# Lamp_Logic_Board_11.net
KiCad netlist of a schematic drawn in EAGLE
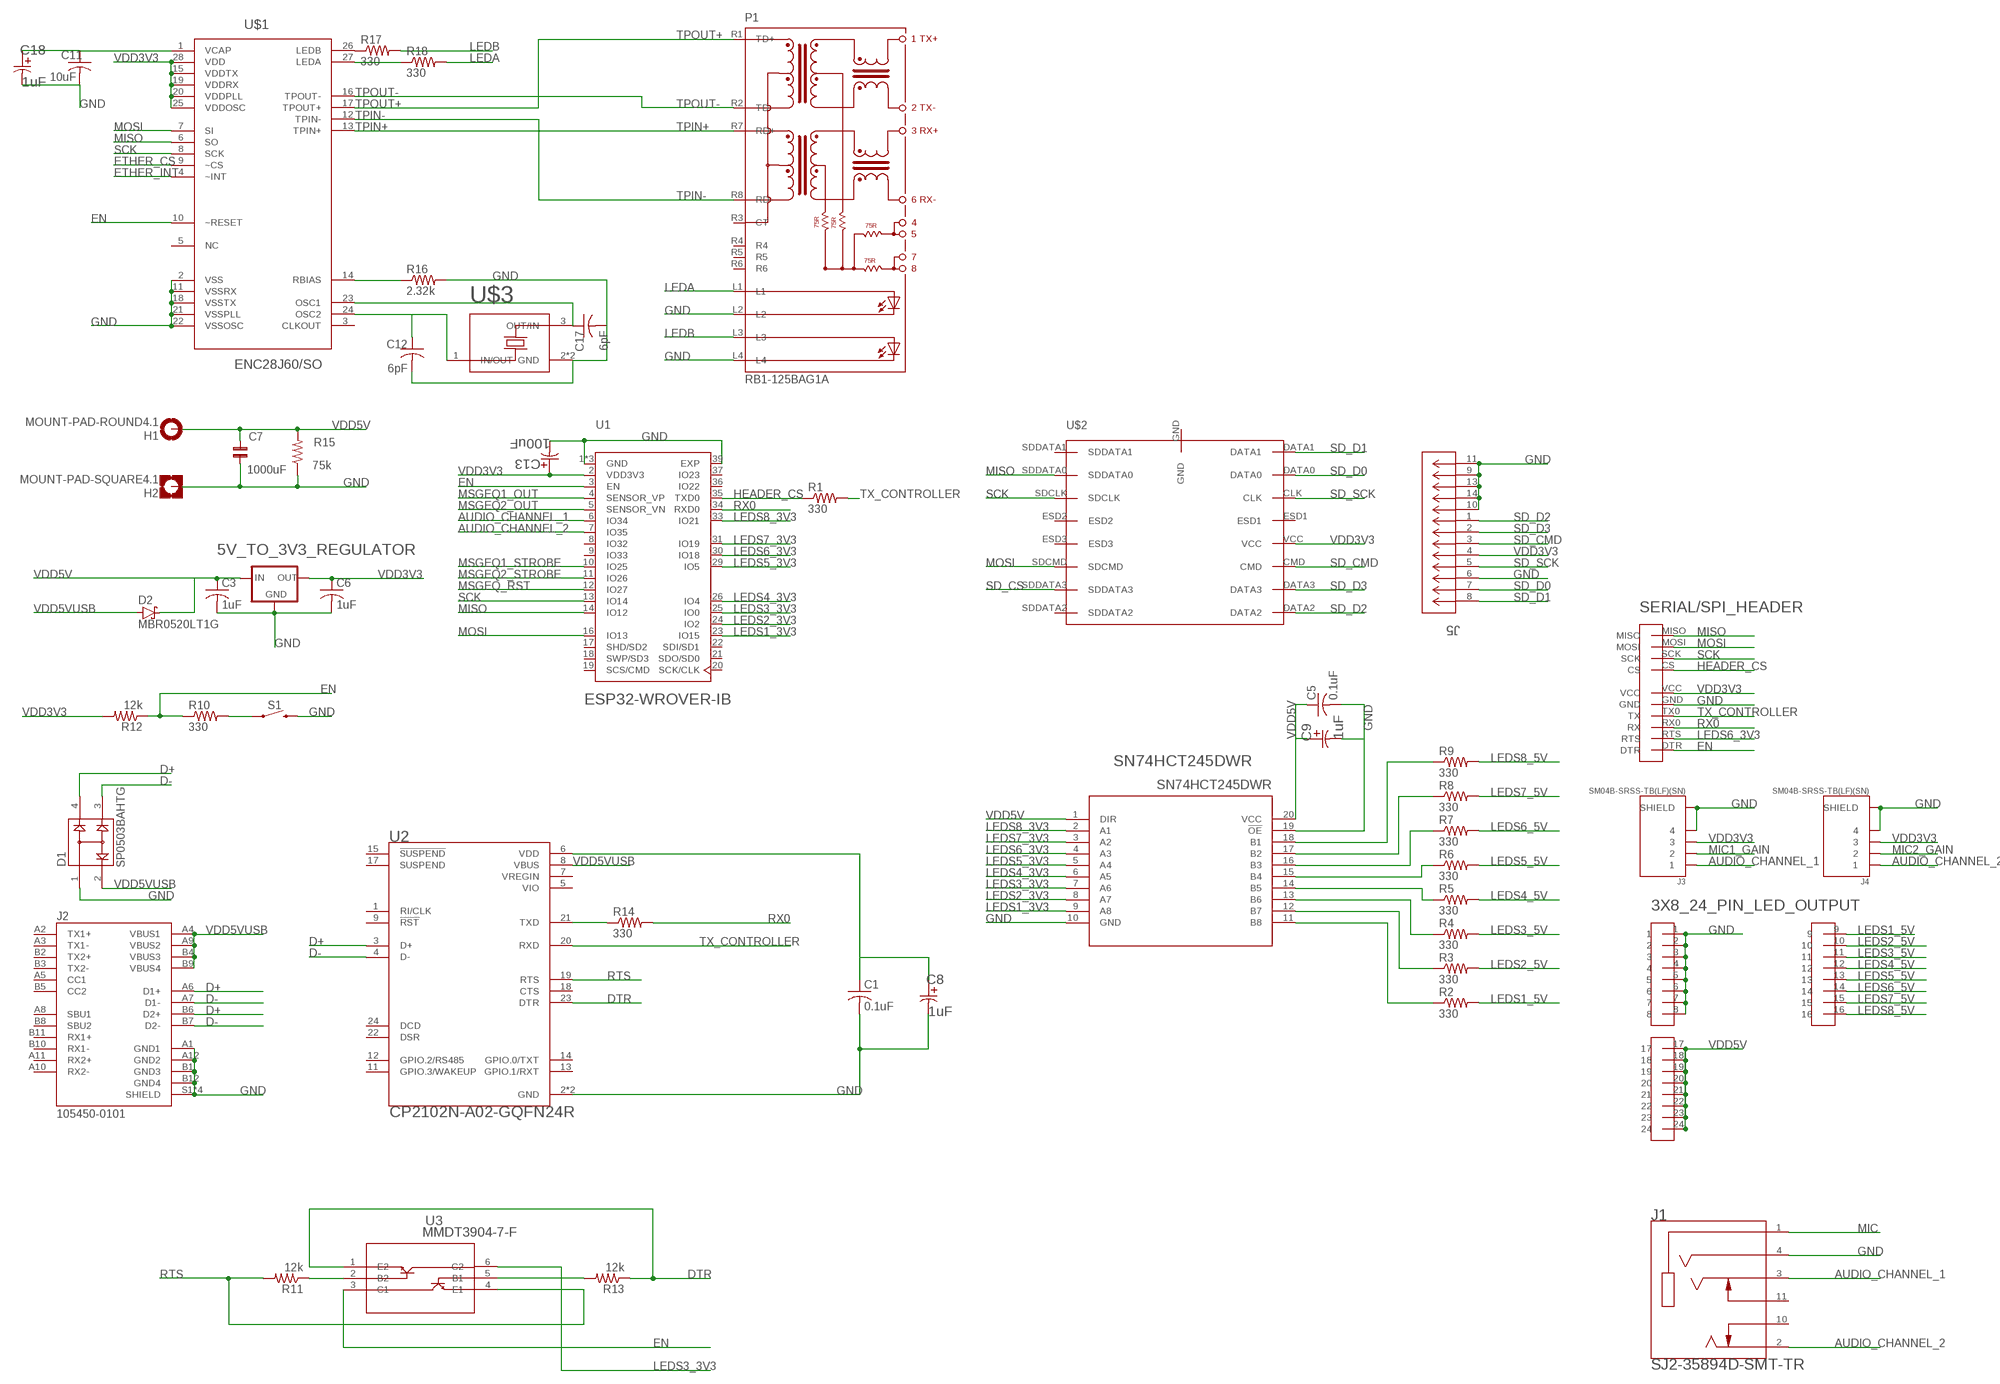
[diagram p0: schematic, sheet 1]

(export (version "E")
  (design (tool "Eeschema 10.0.6"))
  (components
    (comp (ref "3X8_24_PIN_LED_OUTPUT")
      (value "3X8PINHEAD")
      (footprint "eagle-import:3X8PINHEAD")
      (libsource (lib "eagle-import") (part "3X8PINHEAD"))
    )
    (comp (ref "5V_TO_3V3_REGULATOR")
      (value "LM1117MP-1.8")
      (footprint "eagle-import:SOT223")
      (fields (field (name "MF") "Texas Instruments"))
      (libsource (lib "eagle-import") (part "LM1117?-MP1.8"))
    )
    (comp (ref "C1")
      (value "0.1uF")
      (footprint "eagle-import:C0402")
      (libsource (lib "eagle-import") (part "C-USC0402"))
    )
    (comp (ref "C3")
      (value "1uF")
      (footprint "eagle-import:C0402")
      (libsource (lib "eagle-import") (part "C-USC0402"))
    )
    (comp (ref "C5")
      (value "0.1uF")
      (footprint "eagle-import:C0805")
      (libsource (lib "eagle-import") (part "C-USC0805"))
    )
    (comp (ref "C6")
      (value "1uF")
      (footprint "eagle-import:C0402")
      (libsource (lib "eagle-import") (part "C-USC0402"))
    )
    (comp (ref "C7")
      (value "1000uF")
      (footprint "eagle-import:ENP2,0-5")
      (libsource (lib "eagle-import") (part "C-BP-2,0X5"))
    )
    (comp (ref "C8")
      (value "1uF")
      (footprint "eagle-import:CAP_EEFC_B")
      (fields (field (name "MANUFACTURER_PART_NUMBER") "EEEFC1V1R0R"))
      (libsource (lib "eagle-import") (part "EEEFC1V1R0R"))
    )
    (comp (ref "C9")
      (value "1uF")
      (footprint "eagle-import:CAP_EEFC_B")
      (fields (field (name "MANUFACTURER_PART_NUMBER") "EEEFC1V1R0R"))
      (libsource (lib "eagle-import") (part "EEEFC1V1R0R"))
    )
    (comp (ref "C11")
      (value "10uF")
      (footprint "eagle-import:C0402")
      (libsource (lib "eagle-import") (part "C-USC0402"))
    )
    (comp (ref "C12")
      (value "6pF")
      (footprint "eagle-import:C0402")
      (libsource (lib "eagle-import") (part "C-USC0402"))
    )
    (comp (ref "C13")
      (value "100uF")
      (footprint "eagle-import:CAP_EEFC_B")
      (fields (field (name "MANUFACTURER_PART_NUMBER") "EEEFC1V1R0R"))
      (libsource (lib "eagle-import") (part "EEEFC1V1R0R"))
    )
    (comp (ref "C17")
      (value "6pF")
      (footprint "eagle-import:C0402")
      (libsource (lib "eagle-import") (part "C-USC0402"))
    )
    (comp (ref "C18")
      (value "1uF")
      (footprint "eagle-import:CAP_EEFC_B")
      (fields (field (name "MANUFACTURER_PART_NUMBER") "EEEFC1V1R0R"))
      (libsource (lib "eagle-import") (part "EEEFC1V1R0R"))
    )
    (comp (ref "D1")
      (value "SP0503BAHTG")
      (footprint "eagle-import:SOT143")
      (fields (field (name "DIGI-KEY_PART_NUMBER") "F2715CT-ND") (field (name "MF") "Littelfuse Inc."))
      (libsource (lib "eagle-import") (part "SP0503BAHTG"))
    )
    (comp (ref "D2")
      (value "MBR0520LT1G")
      (footprint "eagle-import:SOD-123")
      (fields
        (field (name "DIGIKEY_PART_NUMBER") "MBR0520LT1GOSTR-ND")
        (field (name "MANUFACTURER") "ON Semiconductor")
        (field (name "CREATED_BY") "PCBLayout.com")
      )
      (libsource (lib "eagle-import") (part "MBR0520LT1G"))
    )
    (comp (ref "H1")
      (value "MOUNT-PAD-ROUND4.1")
      (footprint "eagle-import:4,1-PAD")
      (libsource (lib "eagle-import") (part "MOUNT-PAD-ROUND4.1"))
    )
    (comp (ref "H2")
      (value "MOUNT-PAD-SQUARE4.1")
      (footprint "eagle-import:4,1-PAD-SQUARE")
      (libsource (lib "eagle-import") (part "MOUNT-PAD-SQUARE4.1"))
    )
    (comp (ref "J1")
      (value "SJ2-35894D-SMT-TR")
      (footprint "eagle-import:CUI_SJ2-35894D-SMT-TR")
      (fields (field (name "DIGI-KEY_PART_NUMBER") "CP-SJ2-35894D-SMT-CT-ND") (field (name "MF") "CUI Inc."))
      (libsource (lib "eagle-import") (part "SJ2-35894D-SMT-TR"))
    )
    (comp (ref "J2")
      (value "105450-0101")
      (footprint "eagle-import:MOLEX_105450-0101")
      (fields
        (field (name "DIGI-KEY_PART_NUMBER") "WM12856CT-ND")
        (field (name "MF") "Molex")
        (field (name "MP") "1054500101")
      )
      (libsource (lib "eagle-import") (part "105450-0101"))
    )
    (comp (ref "J3")
      (value "SM04B-SRSS-TB(LF)(SN)")
      (footprint "eagle-import:JST_SM04B-SRSS-TB(LF)(SN)")
      (fields (field (name "MF") "JST Sales") (field (name "MP") "SM04B-SRSS-TB_LF__SN_"))
      (libsource (lib "eagle-import") (part "SM04B-SRSS-TB(LF)(SN)"))
    )
    (comp (ref "J4")
      (value "SM04B-SRSS-TB(LF)(SN)")
      (footprint "eagle-import:JST_SM04B-SRSS-TB(LF)(SN)")
      (fields (field (name "MF") "JST Sales") (field (name "MP") "SM04B-SRSS-TB_LF__SN_"))
      (libsource (lib "eagle-import") (part "SM04B-SRSS-TB(LF)(SN)"))
    )
    (comp (ref "J5")
      (value "LLC")
      (footprint "eagle-import:CON00218_8")
      (libsource (lib "eagle-import") (part "LLC"))
    )
    (comp (ref "P1")
      (value "RB1-125BAG1A")
      (footprint "eagle-import:WIZNET_RB1-125BAG1A")
      (fields (field (name "MF") "WIZnet"))
      (libsource (lib "eagle-import") (part "RB1-125BAG1A"))
    )
    (comp (ref "R1")
      (value "330")
      (footprint "eagle-import:R1206")
      (libsource (lib "eagle-import") (part "R-US_R1206"))
    )
    (comp (ref "R2")
      (value "330")
      (footprint "eagle-import:R1206")
      (libsource (lib "eagle-import") (part "R-US_R1206"))
    )
    (comp (ref "R3")
      (value "330")
      (footprint "eagle-import:R1206")
      (libsource (lib "eagle-import") (part "R-US_R1206"))
    )
    (comp (ref "R4")
      (value "330")
      (footprint "eagle-import:R1206")
      (libsource (lib "eagle-import") (part "R-US_R1206"))
    )
    (comp (ref "R5")
      (value "330")
      (footprint "eagle-import:R1206")
      (libsource (lib "eagle-import") (part "R-US_R1206"))
    )
    (comp (ref "R6")
      (value "330")
      (footprint "eagle-import:R1206")
      (libsource (lib "eagle-import") (part "R-US_R1206"))
    )
    (comp (ref "R7")
      (value "330")
      (footprint "eagle-import:R1206")
      (libsource (lib "eagle-import") (part "R-US_R1206"))
    )
    (comp (ref "R8")
      (value "330")
      (footprint "eagle-import:R1206")
      (libsource (lib "eagle-import") (part "R-US_R1206"))
    )
    (comp (ref "R9")
      (value "330")
      (footprint "eagle-import:R1206")
      (libsource (lib "eagle-import") (part "R-US_R1206"))
    )
    (comp (ref "R10")
      (value "330")
      (footprint "eagle-import:R1206")
      (libsource (lib "eagle-import") (part "R-US_R1206"))
    )
    (comp (ref "R11")
      (value "12k")
      (footprint "eagle-import:R1206")
      (libsource (lib "eagle-import") (part "R-US_R1206"))
    )
    (comp (ref "R12")
      (value "12k")
      (footprint "eagle-import:R1206")
      (libsource (lib "eagle-import") (part "R-US_R1206"))
    )
    (comp (ref "R13")
      (value "12k")
      (footprint "eagle-import:R1206")
      (libsource (lib "eagle-import") (part "R-US_R1206"))
    )
    (comp (ref "R14")
      (value "330")
      (footprint "eagle-import:R1206")
      (libsource (lib "eagle-import") (part "R-US_R1206"))
    )
    (comp (ref "R15")
      (value "75k")
      (footprint "eagle-import:0309_12")
      (libsource (lib "eagle-import") (part "R-US_0309/12"))
    )
    (comp (ref "R16")
      (value "2.32k")
      (footprint "eagle-import:R1206")
      (libsource (lib "eagle-import") (part "R-US_R1206"))
    )
    (comp (ref "R17")
      (value "330")
      (footprint "eagle-import:R1206")
      (libsource (lib "eagle-import") (part "R-US_R1206"))
    )
    (comp (ref "R18")
      (value "330")
      (footprint "eagle-import:R1206")
      (libsource (lib "eagle-import") (part "R-US_R1206"))
    )
    (comp (ref "S1")
      (value "MOMENTARY-SWITCH-SPST-SMD-6.0X3.5MM")
      (footprint "eagle-import:TACTILE_SWITCH_SMD_6.0X3.5MM")
      (libsource (lib "eagle-import") (part "MOMENTARY-SWITCH-SPST-SMD-6.0X3.5MM"))
    )
    (comp (ref "SERIAL/SPI_HEADER")
      (value "2X6PINHEAD")
      (footprint "eagle-import:2X6PINHEAD")
      (libsource (lib "eagle-import") (part "2X6PINHEAD"))
    )
    (comp (ref "SN74HCT245DWR")
      (value "SN74HCT245DWR")
      (footprint "eagle-import:DW20")
      (libsource (lib "eagle-import") (part "SN74HCT245DWR"))
    )
    (comp (ref "U$1")
      (value "ENC28J60/SO")
      (footprint "eagle-import:SOIC127P1034X264-28N")
      (fields
        (field (name "DIGI-KEY_PART_NUMBER") "ENC28J60/SS-ND")
        (field (name "MF") "Microchip")
        (field (name "MP") "ENC28J60/SS")
      )
      (libsource (lib "eagle-import") (part "ENC28J60/SO"))
    )
    (comp (ref "U$2")
      (value "CM1624-08DE")
      (footprint "eagle-import:CM1624-08DE")
      (libsource (lib "eagle-import") (part "CM1624-08DE"))
    )
    (comp (ref "U$3")
      (value "ECS-250-10-37B-CTN-TR")
      (footprint "eagle-import:ECS-250-10-37B-CTN-TR")
      (libsource (lib "eagle-import") (part "ECS-250-10-37B-CTN-TR"))
    )
    (comp (ref "U1")
      (value "ESP32-WROVER-IB")
      (footprint "eagle-import:XCVR_ESP32-WROVER-I")
      (fields (field (name "MF") "Espressif Systems") (field (name "MP") "ESP32-WROVER-I"))
      (libsource (lib "eagle-import") (part "ESP32-WROVER-I"))
    )
    (comp (ref "U2")
      (value "CP2102N-A02-GQFN24R")
      (footprint "eagle-import:SILABS_CP2102N-A02-GQFN24R")
      (libsource (lib "eagle-import") (part "CP2102N-A02-GQFN24R"))
    )
    (comp (ref "U3")
      (value "MMDT3904-7-F")
      (footprint "eagle-import:SOT-363")
      (fields (field (name "MANUFACTURER_PART_NUMBER") "MMDT39047F"))
      (libsource (lib "eagle-import") (part "MMDT3904-7-F"))
    )
  )
  (nets
    (net (code "1") (name "AUDIO_CHANNEL_1") (class "Default")
      (node (ref "J1") (pin "3") (pinfunction "RING1_3") (pintype "passive"))
      (node (ref "J3") (pin "1") (pinfunction "1_1") (pintype "passive"))
      (node (ref "U1") (pin "6") (pinfunction "IO34_6") (pintype "input"))
    )
    (net (code "2") (name "AUDIO_CHANNEL_2") (class "Default")
      (node (ref "J1") (pin "2") (pinfunction "TIP_2") (pintype "passive"))
      (node (ref "J4") (pin "1") (pinfunction "1_1") (pintype "passive"))
      (node (ref "U1") (pin "7") (pinfunction "IO35_7") (pintype "input"))
    )
    (net (code "3") (name "D+") (class "Default")
      (node (ref "D1") (pin "4") (pinfunction "4_4") (pintype "passive"))
      (node (ref "J2") (pin "A6") (pinfunction "D1+_A6") (pintype "passive"))
      (node (ref "J2") (pin "B6") (pinfunction "D2+_B6") (pintype "passive"))
      (node (ref "U2") (pin "3") (pinfunction "D+_3") (pintype "bidirectional"))
    )
    (net (code "4") (name "D-") (class "Default")
      (node (ref "D1") (pin "3") (pinfunction "3_3") (pintype "passive"))
      (node (ref "J2") (pin "A7") (pinfunction "D1-_A7") (pintype "passive"))
      (node (ref "J2") (pin "B7") (pinfunction "D2-_B7") (pintype "passive"))
      (node (ref "U2") (pin "4") (pinfunction "D-_4") (pintype "bidirectional"))
    )
    (net (code "5") (name "DTR") (class "Default")
      (node (ref "R13") (pin "1") (pinfunction "1_1") (pintype "passive"))
      (node (ref "U2") (pin "23") (pinfunction "DTR_23") (pintype "bidirectional"))
      (node (ref "U3") (pin "1") (pinfunction "E2_1") (pintype "passive"))
    )
    (net (code "6") (name "EN") (class "Default")
      (node (ref "R10") (pin "1") (pinfunction "1_1") (pintype "passive"))
      (node (ref "R12") (pin "1") (pinfunction "1_1") (pintype "passive"))
      (node (ref "SERIAL/SPI_HEADER") (pin "DTR") (pinfunction "DTR_DTR") (pintype "bidirectional"))
      (node (ref "U$1") (pin "10") (pinfunction "~{RESET}_10") (pintype "input"))
      (node (ref "U1") (pin "3") (pinfunction "EN_3") (pintype "input"))
      (node (ref "U3") (pin "3") (pinfunction "C1_3") (pintype "passive"))
    )
    (net (code "7") (name "ETHER_CS") (class "Default")
      (node (ref "U$1") (pin "9") (pinfunction "~{CS}_9") (pintype "input"))
    )
    (net (code "8") (name "ETHER_INT") (class "Default")
      (node (ref "U$1") (pin "4") (pinfunction "~{INT}_4") (pintype "output"))
    )
    (net (code "9") (name "GND") (class "Default")
      (node (ref "3X8_24_PIN_LED_OUTPUT") (pin "1") (pinfunction "1_1") (pintype "bidirectional"))
      (node (ref "3X8_24_PIN_LED_OUTPUT") (pin "2") (pinfunction "2_2") (pintype "bidirectional"))
      (node (ref "3X8_24_PIN_LED_OUTPUT") (pin "3") (pinfunction "3_3") (pintype "bidirectional"))
      (node (ref "3X8_24_PIN_LED_OUTPUT") (pin "4") (pinfunction "4_4") (pintype "bidirectional"))
      (node (ref "3X8_24_PIN_LED_OUTPUT") (pin "5") (pinfunction "5_5") (pintype "bidirectional"))
      (node (ref "3X8_24_PIN_LED_OUTPUT") (pin "6") (pinfunction "6_6") (pintype "bidirectional"))
      (node (ref "3X8_24_PIN_LED_OUTPUT") (pin "7") (pinfunction "7_7") (pintype "bidirectional"))
      (node (ref "3X8_24_PIN_LED_OUTPUT") (pin "8") (pinfunction "8_8") (pintype "bidirectional"))
      (node (ref "5V_TO_3V3_REGULATOR") (pin "1") (pinfunction "GND_1") (pintype "input"))
      (node (ref "C1") (pin "2") (pinfunction "2_2") (pintype "passive"))
      (node (ref "C11") (pin "2") (pinfunction "2_2") (pintype "passive"))
      (node (ref "C12") (pin "2") (pinfunction "2_2") (pintype "passive"))
      (node (ref "C13") (pin "2") (pinfunction "2_2") (pintype "passive"))
      (node (ref "C17") (pin "2") (pinfunction "2_2") (pintype "passive"))
      (node (ref "C18") (pin "2") (pinfunction "2_2") (pintype "passive"))
      (node (ref "C3") (pin "2") (pinfunction "2_2") (pintype "passive"))
      (node (ref "C5") (pin "2") (pinfunction "2_2") (pintype "passive"))
      (node (ref "C6") (pin "2") (pinfunction "2_2") (pintype "passive"))
      (node (ref "C7") (pin "1") (pinfunction "1_1") (pintype "passive"))
      (node (ref "C8") (pin "2") (pinfunction "2_2") (pintype "passive"))
      (node (ref "C9") (pin "2") (pinfunction "2_2") (pintype "passive"))
      (node (ref "D1") (pin "1") (pinfunction "1_1") (pintype "passive"))
      (node (ref "H2") (pin "B4,1") (pinfunction "MOUNT_B4,1") (pintype "passive"))
      (node (ref "J1") (pin "4") (pinfunction "RING2_4") (pintype "passive"))
      (node (ref "J2") (pin "A1") (pinfunction "GND1_A1") (pintype "passive"))
      (node (ref "J2") (pin "A12") (pinfunction "GND2_A12") (pintype "passive"))
      (node (ref "J2") (pin "B1") (pinfunction "GND3_B1") (pintype "passive"))
      (node (ref "J2") (pin "B12") (pinfunction "GND4_B12") (pintype "passive"))
      (node (ref "J2") (pin "S1") (pinfunction "SHIELD_S1") (pintype "passive"))
      (node (ref "J2") (pin "S2") (pinfunction "SHIELD_S2") (pintype "passive"))
      (node (ref "J2") (pin "S3") (pinfunction "SHIELD_S3") (pintype "passive"))
      (node (ref "J2") (pin "S4") (pinfunction "SHIELD_S4") (pintype "passive"))
      (node (ref "J3") (pin "4") (pinfunction "4_4") (pintype "passive"))
      (node (ref "J3") (pin "S1") (pinfunction "SHIELD_S1") (pintype "passive"))
      (node (ref "J3") (pin "S2") (pinfunction "SHIELD_S2") (pintype "passive"))
      (node (ref "J4") (pin "4") (pinfunction "4_4") (pintype "passive"))
      (node (ref "J4") (pin "S1") (pinfunction "SHIELD_S1") (pintype "passive"))
      (node (ref "J4") (pin "S2") (pinfunction "SHIELD_S2") (pintype "passive"))
      (node (ref "J5") (pin "10") (pinfunction "10_10") (pintype "passive"))
      (node (ref "J5") (pin "11") (pinfunction "11_11") (pintype "passive"))
      (node (ref "J5") (pin "13") (pinfunction "13_13") (pintype "passive"))
      (node (ref "J5") (pin "14") (pinfunction "14_14") (pintype "passive"))
      (node (ref "J5") (pin "6") (pinfunction "6_6") (pintype "passive"))
      (node (ref "J5") (pin "9") (pinfunction "9_9") (pintype "passive"))
      (node (ref "P1") (pin "L2") (pinfunction "L2_L2") (pintype "passive"))
      (node (ref "P1") (pin "L4") (pinfunction "L4_L4") (pintype "passive"))
      (node (ref "R15") (pin "1") (pinfunction "1_1") (pintype "passive"))
      (node (ref "R16") (pin "2") (pinfunction "2_2") (pintype "passive"))
      (node (ref "S1") (pin "2") (pinfunction "2_2") (pintype "passive"))
      (node (ref "SERIAL/SPI_HEADER") (pin "GND") (pinfunction "GND_GND") (pintype "bidirectional"))
      (node (ref "SN74HCT245DWR") (pin "10") (pinfunction "GND_10") (pintype "power_in"))
      (node (ref "SN74HCT245DWR") (pin "19") (pinfunction "~{OE}_19") (pintype "input"))
      (node (ref "U$1") (pin "11") (pinfunction "VSSRX_11") (pintype "power_in"))
      (node (ref "U$1") (pin "18") (pinfunction "VSSTX_18") (pintype "power_in"))
      (node (ref "U$1") (pin "2") (pinfunction "VSS_2") (pintype "power_in"))
      (node (ref "U$1") (pin "21") (pinfunction "VSSPLL_21") (pintype "power_in"))
      (node (ref "U$1") (pin "22") (pinfunction "VSSOSC_22") (pintype "power_in"))
      (node (ref "U$3") (pin "2") (pinfunction "GND_2") (pintype "bidirectional"))
      (node (ref "U$3") (pin "4") (pinfunction "GND_4") (pintype "bidirectional"))
      (node (ref "U1") (pin "1") (pinfunction "GND_1") (pintype "power_in"))
      (node (ref "U1") (pin "15") (pinfunction "GND_15") (pintype "power_in"))
      (node (ref "U1") (pin "38") (pinfunction "GND_38") (pintype "power_in"))
      (node (ref "U1") (pin "39") (pinfunction "EXP_39") (pintype "power_in"))
      (node (ref "U2") (pin "2") (pinfunction "GND_2") (pintype "power_in"))
      (node (ref "U2") (pin "25") (pinfunction "GND_25") (pintype "power_in"))
    )
    (net (code "10") (name "HEADER_CS") (class "Default")
      (node (ref "R1") (pin "1") (pinfunction "1_1") (pintype "passive"))
      (node (ref "SERIAL/SPI_HEADER") (pin "CS") (pinfunction "CS_CS") (pintype "bidirectional"))
      (node (ref "U1") (pin "35") (pinfunction "TXD0_35") (pintype "bidirectional"))
    )
    (net (code "11") (name "LEDA") (class "Default")
      (node (ref "P1") (pin "L1") (pinfunction "L1_L1") (pintype "passive"))
      (node (ref "R18") (pin "2") (pinfunction "2_2") (pintype "passive"))
    )
    (net (code "12") (name "LEDB") (class "Default")
      (node (ref "P1") (pin "L3") (pinfunction "L3_L3") (pintype "passive"))
      (node (ref "R17") (pin "2") (pinfunction "2_2") (pintype "passive"))
    )
    (net (code "13") (name "LEDS1_3V3") (class "Default")
      (node (ref "SN74HCT245DWR") (pin "9") (pinfunction "A8_9") (pintype "bidirectional"))
      (node (ref "U1") (pin "23") (pinfunction "IO15_23") (pintype "bidirectional"))
    )
    (net (code "14") (name "LEDS1_5V") (class "Default")
      (node (ref "3X8_24_PIN_LED_OUTPUT") (pin "9") (pinfunction "9_9") (pintype "bidirectional"))
      (node (ref "R2") (pin "2") (pinfunction "2_2") (pintype "passive"))
    )
    (net (code "15") (name "LEDS2_3V3") (class "Default")
      (node (ref "SN74HCT245DWR") (pin "8") (pinfunction "A7_8") (pintype "bidirectional"))
      (node (ref "U1") (pin "24") (pinfunction "IO2_24") (pintype "bidirectional"))
    )
    (net (code "16") (name "LEDS2_5V") (class "Default")
      (node (ref "3X8_24_PIN_LED_OUTPUT") (pin "10") (pinfunction "10_10") (pintype "bidirectional"))
      (node (ref "R3") (pin "2") (pinfunction "2_2") (pintype "passive"))
    )
    (net (code "17") (name "LEDS3_3V3") (class "Default")
      (node (ref "SN74HCT245DWR") (pin "7") (pinfunction "A6_7") (pintype "bidirectional"))
      (node (ref "U1") (pin "25") (pinfunction "IO0_25") (pintype "bidirectional"))
      (node (ref "U3") (pin "6") (pinfunction "C2_6") (pintype "passive"))
    )
    (net (code "18") (name "LEDS3_5V") (class "Default")
      (node (ref "3X8_24_PIN_LED_OUTPUT") (pin "11") (pinfunction "11_11") (pintype "bidirectional"))
      (node (ref "R4") (pin "2") (pinfunction "2_2") (pintype "passive"))
    )
    (net (code "19") (name "LEDS4_3V3") (class "Default")
      (node (ref "SN74HCT245DWR") (pin "6") (pinfunction "A5_6") (pintype "bidirectional"))
      (node (ref "U1") (pin "26") (pinfunction "IO4_26") (pintype "bidirectional"))
    )
    (net (code "20") (name "LEDS4_5V") (class "Default")
      (node (ref "3X8_24_PIN_LED_OUTPUT") (pin "12") (pinfunction "12_12") (pintype "bidirectional"))
      (node (ref "R5") (pin "2") (pinfunction "2_2") (pintype "passive"))
    )
    (net (code "21") (name "LEDS5_3V3") (class "Default")
      (node (ref "SN74HCT245DWR") (pin "5") (pinfunction "A4_5") (pintype "bidirectional"))
      (node (ref "U1") (pin "29") (pinfunction "IO5_29") (pintype "bidirectional"))
    )
    (net (code "22") (name "LEDS5_5V") (class "Default")
      (node (ref "3X8_24_PIN_LED_OUTPUT") (pin "13") (pinfunction "13_13") (pintype "bidirectional"))
      (node (ref "R6") (pin "2") (pinfunction "2_2") (pintype "passive"))
    )
    (net (code "23") (name "LEDS6_3V3") (class "Default")
      (node (ref "SERIAL/SPI_HEADER") (pin "RTS") (pinfunction "RTS_RTS") (pintype "bidirectional"))
      (node (ref "SN74HCT245DWR") (pin "4") (pinfunction "A3_4") (pintype "bidirectional"))
      (node (ref "U1") (pin "30") (pinfunction "IO18_30") (pintype "bidirectional"))
    )
    (net (code "24") (name "LEDS6_5V") (class "Default")
      (node (ref "3X8_24_PIN_LED_OUTPUT") (pin "14") (pinfunction "14_14") (pintype "bidirectional"))
      (node (ref "R7") (pin "2") (pinfunction "2_2") (pintype "passive"))
    )
    (net (code "25") (name "LEDS7_3V3") (class "Default")
      (node (ref "SN74HCT245DWR") (pin "3") (pinfunction "A2_3") (pintype "bidirectional"))
      (node (ref "U1") (pin "31") (pinfunction "IO19_31") (pintype "bidirectional"))
    )
    (net (code "26") (name "LEDS7_5V") (class "Default")
      (node (ref "3X8_24_PIN_LED_OUTPUT") (pin "15") (pinfunction "15_15") (pintype "bidirectional"))
      (node (ref "R8") (pin "2") (pinfunction "2_2") (pintype "passive"))
    )
    (net (code "27") (name "LEDS8_3V3") (class "Default")
      (node (ref "SN74HCT245DWR") (pin "2") (pinfunction "A1_2") (pintype "bidirectional"))
      (node (ref "U1") (pin "33") (pinfunction "IO21_33") (pintype "bidirectional"))
    )
    (net (code "28") (name "LEDS8_5V") (class "Default")
      (node (ref "3X8_24_PIN_LED_OUTPUT") (pin "16") (pinfunction "16_16") (pintype "bidirectional"))
      (node (ref "R9") (pin "2") (pinfunction "2_2") (pintype "passive"))
    )
    (net (code "29") (name "MIC") (class "Default")
      (node (ref "J1") (pin "1") (pinfunction "SLEEVE_1") (pintype "passive"))
    )
    (net (code "30") (name "MIC1_GAIN") (class "Default")
      (node (ref "J3") (pin "2") (pinfunction "2_2") (pintype "passive"))
    )
    (net (code "31") (name "MIC2_GAIN") (class "Default")
      (node (ref "J4") (pin "2") (pinfunction "2_2") (pintype "passive"))
    )
    (net (code "32") (name "MISO") (class "Default")
      (node (ref "SERIAL/SPI_HEADER") (pin "MISO") (pinfunction "MISO_MISO") (pintype "bidirectional"))
      (node (ref "U$1") (pin "6") (pinfunction "SO_6") (pintype "output"))
      (node (ref "U$2") (pin "SDDATA0") (pinfunction "SDDATA0_SDDATA0") (pintype "bidirectional"))
      (node (ref "U1") (pin "14") (pinfunction "IO12_14") (pintype "bidirectional"))
    )
    (net (code "33") (name "MOSI") (class "Default")
      (node (ref "SERIAL/SPI_HEADER") (pin "MOSI") (pinfunction "MOSI_MOSI") (pintype "bidirectional"))
      (node (ref "U$1") (pin "7") (pinfunction "SI_7") (pintype "input"))
      (node (ref "U$2") (pin "SDCMD") (pinfunction "SDCMD_SDCMD") (pintype "bidirectional"))
      (node (ref "U1") (pin "16") (pinfunction "IO13_16") (pintype "bidirectional"))
    )
    (net (code "34") (name "MSGEQ1_OUT") (class "Default")
      (node (ref "U1") (pin "4") (pinfunction "SENSOR_VP_4") (pintype "input"))
    )
    (net (code "35") (name "MSGEQ1_STROBE") (class "Default")
      (node (ref "U1") (pin "10") (pinfunction "IO25_10") (pintype "bidirectional"))
    )
    (net (code "36") (name "MSGEQ2_OUT") (class "Default")
      (node (ref "U1") (pin "5") (pinfunction "SENSOR_VN_5") (pintype "input"))
    )
    (net (code "37") (name "MSGEQ2_STROBE") (class "Default")
      (node (ref "U1") (pin "11") (pinfunction "IO26_11") (pintype "bidirectional"))
    )
    (net (code "38") (name "MSGEQ_RST") (class "Default")
      (node (ref "U1") (pin "12") (pinfunction "IO27_12") (pintype "bidirectional"))
    )
    (net (code "39") (name "Net-(R10-Pad2)") (class "Default")
      (node (ref "R10") (pin "2") (pinfunction "2_2") (pintype "passive"))
      (node (ref "S1") (pin "1") (pinfunction "1_1") (pintype "passive"))
    )
    (net (code "40") (name "Net-(SN74HCT245DWR-B1)") (class "Default")
      (node (ref "R9") (pin "1") (pinfunction "1_1") (pintype "passive"))
      (node (ref "SN74HCT245DWR") (pin "18") (pinfunction "B1_18") (pintype "bidirectional"))
    )
    (net (code "41") (name "Net-(SN74HCT245DWR-B2)") (class "Default")
      (node (ref "R8") (pin "1") (pinfunction "1_1") (pintype "passive"))
      (node (ref "SN74HCT245DWR") (pin "17") (pinfunction "B2_17") (pintype "bidirectional"))
    )
    (net (code "42") (name "Net-(SN74HCT245DWR-B3)") (class "Default")
      (node (ref "R7") (pin "1") (pinfunction "1_1") (pintype "passive"))
      (node (ref "SN74HCT245DWR") (pin "16") (pinfunction "B3_16") (pintype "bidirectional"))
    )
    (net (code "43") (name "Net-(SN74HCT245DWR-B4)") (class "Default")
      (node (ref "R6") (pin "1") (pinfunction "1_1") (pintype "passive"))
      (node (ref "SN74HCT245DWR") (pin "15") (pinfunction "B4_15") (pintype "bidirectional"))
    )
    (net (code "44") (name "Net-(SN74HCT245DWR-B5)") (class "Default")
      (node (ref "R5") (pin "1") (pinfunction "1_1") (pintype "passive"))
      (node (ref "SN74HCT245DWR") (pin "14") (pinfunction "B5_14") (pintype "bidirectional"))
    )
    (net (code "45") (name "Net-(SN74HCT245DWR-B6)") (class "Default")
      (node (ref "R4") (pin "1") (pinfunction "1_1") (pintype "passive"))
      (node (ref "SN74HCT245DWR") (pin "13") (pinfunction "B6_13") (pintype "bidirectional"))
    )
    (net (code "46") (name "Net-(SN74HCT245DWR-B7)") (class "Default")
      (node (ref "R3") (pin "1") (pinfunction "1_1") (pintype "passive"))
      (node (ref "SN74HCT245DWR") (pin "12") (pinfunction "B7_12") (pintype "bidirectional"))
    )
    (net (code "47") (name "Net-(SN74HCT245DWR-B8)") (class "Default")
      (node (ref "R2") (pin "1") (pinfunction "1_1") (pintype "passive"))
      (node (ref "SN74HCT245DWR") (pin "11") (pinfunction "B8_11") (pintype "bidirectional"))
    )
    (net (code "48") (name "Net-(U$1-LEDA)") (class "Default")
      (node (ref "R18") (pin "1") (pinfunction "1_1") (pintype "passive"))
      (node (ref "U$1") (pin "27") (pinfunction "LEDA_27") (pintype "output"))
    )
    (net (code "49") (name "Net-(U$1-LEDB)") (class "Default")
      (node (ref "R17") (pin "1") (pinfunction "1_1") (pintype "passive"))
      (node (ref "U$1") (pin "26") (pinfunction "LEDB_26") (pintype "output"))
    )
    (net (code "50") (name "Net-(U$1-OSC1)") (class "Default")
      (node (ref "C17") (pin "1") (pinfunction "1_1") (pintype "passive"))
      (node (ref "U$1") (pin "23") (pinfunction "OSC1_23") (pintype "input"))
      (node (ref "U$3") (pin "3") (pinfunction "OUT/IN_3") (pintype "bidirectional"))
    )
    (net (code "51") (name "Net-(U$1-OSC2)") (class "Default")
      (node (ref "C12") (pin "1") (pinfunction "1_1") (pintype "passive"))
      (node (ref "U$1") (pin "24") (pinfunction "OSC2_24") (pintype "output"))
      (node (ref "U$3") (pin "1") (pinfunction "IN/OUT_1") (pintype "bidirectional"))
    )
    (net (code "52") (name "Net-(U$1-RBIAS)") (class "Default")
      (node (ref "R16") (pin "1") (pinfunction "1_1") (pintype "passive"))
      (node (ref "U$1") (pin "14") (pinfunction "RBIAS_14") (pintype "input"))
    )
    (net (code "53") (name "Net-(U$1-VCAP)") (class "Default")
      (node (ref "C11") (pin "1") (pinfunction "1_1") (pintype "passive"))
      (node (ref "C18") (pin "1") (pinfunction "1_1") (pintype "passive"))
      (node (ref "U$1") (pin "1") (pinfunction "VCAP_1") (pintype "input"))
    )
    (net (code "54") (name "Net-(U2-TXD)") (class "Default")
      (node (ref "R14") (pin "1") (pinfunction "1_1") (pintype "passive"))
      (node (ref "U2") (pin "21") (pinfunction "TXD_21") (pintype "output"))
    )
    (net (code "55") (name "Net-(U2-VDD)") (class "Default")
      (node (ref "C1") (pin "1") (pinfunction "1_1") (pintype "passive"))
      (node (ref "C8") (pin "1") (pinfunction "1_1") (pintype "passive"))
      (node (ref "U2") (pin "6") (pinfunction "VDD_6") (pintype "power_in"))
    )
    (net (code "56") (name "Net-(U3-B1)") (class "Default")
      (node (ref "R13") (pin "2") (pinfunction "2_2") (pintype "passive"))
      (node (ref "U3") (pin "5") (pinfunction "B1_5") (pintype "passive"))
    )
    (net (code "57") (name "Net-(U3-B2)") (class "Default")
      (node (ref "R11") (pin "1") (pinfunction "1_1") (pintype "passive"))
      (node (ref "U3") (pin "2") (pinfunction "B2_2") (pintype "passive"))
    )
    (net (code "58") (name "RTS") (class "Default")
      (node (ref "R11") (pin "2") (pinfunction "2_2") (pintype "passive"))
      (node (ref "U2") (pin "19") (pinfunction "RTS_19") (pintype "output"))
      (node (ref "U3") (pin "4") (pinfunction "E1_4") (pintype "passive"))
    )
    (net (code "59") (name "RX0") (class "Default")
      (node (ref "R14") (pin "2") (pinfunction "2_2") (pintype "passive"))
      (node (ref "SERIAL/SPI_HEADER") (pin "RX0") (pinfunction "RX_RX0") (pintype "bidirectional"))
      (node (ref "U1") (pin "34") (pinfunction "RXD0_34") (pintype "bidirectional"))
    )
    (net (code "60") (name "SCK") (class "Default")
      (node (ref "SERIAL/SPI_HEADER") (pin "SCK") (pinfunction "SCK_SCK") (pintype "bidirectional"))
      (node (ref "U$1") (pin "8") (pinfunction "SCK_8") (pintype "input"))
      (node (ref "U$2") (pin "SDCLK") (pinfunction "SDCLK_SDCLK") (pintype "bidirectional"))
      (node (ref "U1") (pin "13") (pinfunction "IO14_13") (pintype "bidirectional"))
    )
    (net (code "61") (name "SD_CMD") (class "Default")
      (node (ref "J5") (pin "3") (pinfunction "3_3") (pintype "passive"))
      (node (ref "U$2") (pin "CMD") (pinfunction "CMD_CMD") (pintype "bidirectional"))
    )
    (net (code "62") (name "SD_CS") (class "Default")
      (node (ref "U$2") (pin "SDDATA3") (pinfunction "SDDATA3_SDDATA3") (pintype "bidirectional"))
    )
    (net (code "63") (name "SD_D0") (class "Default")
      (node (ref "J5") (pin "7") (pinfunction "7_7") (pintype "passive"))
      (node (ref "U$2") (pin "DATA0") (pinfunction "DATA0_DATA0") (pintype "bidirectional"))
    )
    (net (code "64") (name "SD_D1") (class "Default")
      (node (ref "J5") (pin "8") (pinfunction "8_8") (pintype "passive"))
      (node (ref "U$2") (pin "DATA1") (pinfunction "DATA1_DATA1") (pintype "bidirectional"))
    )
    (net (code "65") (name "SD_D2") (class "Default")
      (node (ref "J5") (pin "1") (pinfunction "1_1") (pintype "passive"))
      (node (ref "U$2") (pin "DATA2") (pinfunction "DATA2_DATA2") (pintype "bidirectional"))
    )
    (net (code "66") (name "SD_D3") (class "Default")
      (node (ref "J5") (pin "2") (pinfunction "2_2") (pintype "passive"))
      (node (ref "U$2") (pin "DATA3") (pinfunction "DATA3_DATA3") (pintype "bidirectional"))
    )
    (net (code "67") (name "SD_SCK") (class "Default")
      (node (ref "J5") (pin "5") (pinfunction "5_5") (pintype "passive"))
      (node (ref "U$2") (pin "CLK") (pinfunction "CLK_CLK") (pintype "bidirectional"))
    )
    (net (code "68") (name "TPIN+") (class "Default")
      (node (ref "P1") (pin "R7") (pinfunction "RD+_R7") (pintype "input"))
      (node (ref "U$1") (pin "13") (pinfunction "TPIN+_13") (pintype "input"))
    )
    (net (code "69") (name "TPIN-") (class "Default")
      (node (ref "P1") (pin "R8") (pinfunction "RD-_R8") (pintype "input"))
      (node (ref "U$1") (pin "12") (pinfunction "TPIN-_12") (pintype "input"))
    )
    (net (code "70") (name "TPOUT+") (class "Default")
      (node (ref "P1") (pin "R1") (pinfunction "TD+_R1") (pintype "input"))
      (node (ref "U$1") (pin "17") (pinfunction "TPOUT+_17") (pintype "output"))
    )
    (net (code "71") (name "TPOUT-") (class "Default")
      (node (ref "P1") (pin "R2") (pinfunction "TD-_R2") (pintype "input"))
      (node (ref "U$1") (pin "16") (pinfunction "TPOUT-_16") (pintype "output"))
    )
    (net (code "72") (name "TX_CONTROLLER") (class "Default")
      (node (ref "R1") (pin "2") (pinfunction "2_2") (pintype "passive"))
      (node (ref "SERIAL/SPI_HEADER") (pin "TX0") (pinfunction "TX_TX0") (pintype "bidirectional"))
      (node (ref "U2") (pin "20") (pinfunction "RXD_20") (pintype "input"))
    )
    (net (code "73") (name "VDD3V3") (class "Default")
      (node (ref "5V_TO_3V3_REGULATOR") (pin "2") (pinfunction "OUT_2") (pintype "passive"))
      (node (ref "5V_TO_3V3_REGULATOR") (pin "4") (pinfunction "OUT_4") (pintype "passive"))
      (node (ref "C13") (pin "1") (pinfunction "1_1") (pintype "passive"))
      (node (ref "C6") (pin "1") (pinfunction "1_1") (pintype "passive"))
      (node (ref "J3") (pin "3") (pinfunction "3_3") (pintype "passive"))
      (node (ref "J4") (pin "3") (pinfunction "3_3") (pintype "passive"))
      (node (ref "J5") (pin "4") (pinfunction "4_4") (pintype "passive"))
      (node (ref "R12") (pin "2") (pinfunction "2_2") (pintype "passive"))
      (node (ref "SERIAL/SPI_HEADER") (pin "VCC") (pinfunction "VCC_VCC") (pintype "bidirectional"))
      (node (ref "U$1") (pin "15") (pinfunction "VDDTX_15") (pintype "power_in"))
      (node (ref "U$1") (pin "19") (pinfunction "VDDRX_19") (pintype "power_in"))
      (node (ref "U$1") (pin "20") (pinfunction "VDDPLL_20") (pintype "power_in"))
      (node (ref "U$1") (pin "25") (pinfunction "VDDOSC_25") (pintype "power_in"))
      (node (ref "U$1") (pin "28") (pinfunction "VDD_28") (pintype "power_in"))
      (node (ref "U$2") (pin "VCC") (pinfunction "VCC_VCC") (pintype "bidirectional"))
      (node (ref "U1") (pin "2") (pinfunction "VDD3V3_2") (pintype "power_in"))
    )
    (net (code "74") (name "VDD5V") (class "Default")
      (node (ref "3X8_24_PIN_LED_OUTPUT") (pin "17") (pinfunction "17_17") (pintype "bidirectional"))
      (node (ref "3X8_24_PIN_LED_OUTPUT") (pin "18") (pinfunction "18_18") (pintype "bidirectional"))
      (node (ref "3X8_24_PIN_LED_OUTPUT") (pin "19") (pinfunction "19_19") (pintype "bidirectional"))
      (node (ref "3X8_24_PIN_LED_OUTPUT") (pin "20") (pinfunction "20_20") (pintype "bidirectional"))
      (node (ref "3X8_24_PIN_LED_OUTPUT") (pin "21") (pinfunction "21_21") (pintype "bidirectional"))
      (node (ref "3X8_24_PIN_LED_OUTPUT") (pin "22") (pinfunction "22_22") (pintype "bidirectional"))
      (node (ref "3X8_24_PIN_LED_OUTPUT") (pin "23") (pinfunction "23_23") (pintype "bidirectional"))
      (node (ref "3X8_24_PIN_LED_OUTPUT") (pin "24") (pinfunction "24_24") (pintype "bidirectional"))
      (node (ref "5V_TO_3V3_REGULATOR") (pin "3") (pinfunction "IN_3") (pintype "input"))
      (node (ref "C3") (pin "1") (pinfunction "1_1") (pintype "passive"))
      (node (ref "C5") (pin "1") (pinfunction "1_1") (pintype "passive"))
      (node (ref "C7") (pin "2") (pinfunction "2_2") (pintype "passive"))
      (node (ref "C9") (pin "1") (pinfunction "1_1") (pintype "passive"))
      (node (ref "D2") (pin "C") (pinfunction "C_C") (pintype "passive"))
      (node (ref "H1") (pin "B4,1") (pinfunction "MOUNT_B4,1") (pintype "passive"))
      (node (ref "R15") (pin "2") (pinfunction "2_2") (pintype "passive"))
      (node (ref "SN74HCT245DWR") (pin "1") (pinfunction "DIR_1") (pintype "input"))
      (node (ref "SN74HCT245DWR") (pin "20") (pinfunction "VCC_20") (pintype "power_in"))
    )
    (net (code "75") (name "VDD5VUSB") (class "Default")
      (node (ref "D1") (pin "2") (pinfunction "2_2") (pintype "passive"))
      (node (ref "D2") (pin "A") (pinfunction "A_A") (pintype "passive"))
      (node (ref "J2") (pin "A4") (pinfunction "VBUS1_A4") (pintype "passive"))
      (node (ref "J2") (pin "A9") (pinfunction "VBUS2_A9") (pintype "passive"))
      (node (ref "J2") (pin "B4") (pinfunction "VBUS3_B4") (pintype "passive"))
      (node (ref "J2") (pin "B9") (pinfunction "VBUS4_B9") (pintype "passive"))
      (node (ref "U2") (pin "8") (pinfunction "VBUS_8") (pintype "power_in"))
    )
    (net (code "76") (name "VREGIN") (class "Default")
      (node (ref "U2") (pin "7") (pinfunction "VREGIN_7") (pintype "power_in"))
    )
    (net (code "77") (name "unconnected-(J1-RING1_SWITCH-Pad11)") (class "Default")
      (node (ref "J1") (pin "11") (pinfunction "RING1_SWITCH_11") (pintype "passive"))
    )
    (net (code "78") (name "unconnected-(J1-TIP_SWITCH-Pad10)") (class "Default")
      (node (ref "J1") (pin "10") (pinfunction "TIP_SWITCH_10") (pintype "passive"))
    )
    (net (code "79") (name "unconnected-(J2-CC1-PadA5)") (class "Default")
      (node (ref "J2") (pin "A5") (pinfunction "CC1_A5") (pintype "passive"))
    )
    (net (code "80") (name "unconnected-(J2-CC2-PadB5)") (class "Default")
      (node (ref "J2") (pin "B5") (pinfunction "CC2_B5") (pintype "passive"))
    )
    (net (code "81") (name "unconnected-(J2-RX1+-PadB11)") (class "Default")
      (node (ref "J2") (pin "B11") (pinfunction "RX1+_B11") (pintype "passive"))
    )
    (net (code "82") (name "unconnected-(J2-RX1--PadB10)") (class "Default")
      (node (ref "J2") (pin "B10") (pinfunction "RX1-_B10") (pintype "passive"))
    )
    (net (code "83") (name "unconnected-(J2-RX2+-PadA11)") (class "Default")
      (node (ref "J2") (pin "A11") (pinfunction "RX2+_A11") (pintype "passive"))
    )
    (net (code "84") (name "unconnected-(J2-RX2--PadA10)") (class "Default")
      (node (ref "J2") (pin "A10") (pinfunction "RX2-_A10") (pintype "passive"))
    )
    (net (code "85") (name "unconnected-(J2-SBU1-PadA8)") (class "Default")
      (node (ref "J2") (pin "A8") (pinfunction "SBU1_A8") (pintype "passive"))
    )
    (net (code "86") (name "unconnected-(J2-SBU2-PadB8)") (class "Default")
      (node (ref "J2") (pin "B8") (pinfunction "SBU2_B8") (pintype "passive"))
    )
    (net (code "87") (name "unconnected-(J2-TX1+-PadA2)") (class "Default")
      (node (ref "J2") (pin "A2") (pinfunction "TX1+_A2") (pintype "passive"))
    )
    (net (code "88") (name "unconnected-(J2-TX1--PadA3)") (class "Default")
      (node (ref "J2") (pin "A3") (pinfunction "TX1-_A3") (pintype "passive"))
    )
    (net (code "89") (name "unconnected-(J2-TX2+-PadB2)") (class "Default")
      (node (ref "J2") (pin "B2") (pinfunction "TX2+_B2") (pintype "passive"))
    )
    (net (code "90") (name "unconnected-(J2-TX2--PadB3)") (class "Default")
      (node (ref "J2") (pin "B3") (pinfunction "TX2-_B3") (pintype "passive"))
    )
    (net (code "91") (name "unconnected-(P1-CT-PadR3)") (class "Default")
      (node (ref "P1") (pin "R3") (pinfunction "CT_R3") (pintype "input"))
    )
    (net (code "92") (name "unconnected-(P1-PadR4)") (class "Default")
      (node (ref "P1") (pin "R4") (pinfunction "R4_R4") (pintype "input"))
    )
    (net (code "93") (name "unconnected-(P1-PadR5)") (class "Default")
      (node (ref "P1") (pin "R5") (pinfunction "R5_R5") (pintype "input"))
    )
    (net (code "94") (name "unconnected-(P1-PadR6)") (class "Default")
      (node (ref "P1") (pin "R6") (pinfunction "R6_R6") (pintype "input"))
    )
    (net (code "95") (name "unconnected-(U$1-CLKOUT-Pad3)") (class "Default")
      (node (ref "U$1") (pin "3") (pinfunction "CLKOUT_3") (pintype "output"))
    )
    (net (code "96") (name "unconnected-(U$1-NC-Pad5)") (class "Default")
      (node (ref "U$1") (pin "5") (pinfunction "NC_5") (pintype "no_connect"))
    )
    (net (code "97") (name "unconnected-(U$2-PadESD1)") (class "Default")
      (node (ref "U$2") (pin "ESD1") (pinfunction "ESD1_ESD1") (pintype "bidirectional"))
    )
    (net (code "98") (name "unconnected-(U$2-PadESD2)") (class "Default")
      (node (ref "U$2") (pin "ESD2") (pinfunction "ESD2_ESD2") (pintype "bidirectional"))
    )
    (net (code "99") (name "unconnected-(U$2-PadESD3)") (class "Default")
      (node (ref "U$2") (pin "ESD3") (pinfunction "ESD3_ESD3") (pintype "bidirectional"))
    )
    (net (code "100") (name "unconnected-(U$2-PadGND)") (class "Default")
      (node (ref "U$2") (pin "GND") (pinfunction "GND_GND") (pintype "bidirectional"))
    )
    (net (code "101") (name "unconnected-(U$2-PadSDDATA1)") (class "Default")
      (node (ref "U$2") (pin "SDDATA1") (pinfunction "SDDATA1_SDDATA1") (pintype "bidirectional"))
    )
    (net (code "102") (name "unconnected-(U$2-PadSDDATA2)") (class "Default")
      (node (ref "U$2") (pin "SDDATA2") (pinfunction "SDDATA2_SDDATA2") (pintype "bidirectional"))
    )
    (net (code "103") (name "unconnected-(U1-IO22-Pad36)") (class "Default")
      (node (ref "U1") (pin "36") (pinfunction "IO22_36") (pintype "bidirectional"))
    )
    (net (code "104") (name "unconnected-(U1-IO23-Pad37)") (class "Default")
      (node (ref "U1") (pin "37") (pinfunction "IO23_37") (pintype "bidirectional"))
    )
    (net (code "105") (name "unconnected-(U1-IO32-Pad8)") (class "Default")
      (node (ref "U1") (pin "8") (pinfunction "IO32_8") (pintype "bidirectional"))
    )
    (net (code "106") (name "unconnected-(U1-IO33-Pad9)") (class "Default")
      (node (ref "U1") (pin "9") (pinfunction "IO33_9") (pintype "bidirectional"))
    )
    (net (code "107") (name "unconnected-(U1-SCK{slash}CLK-Pad20)") (class "Default")
      (node (ref "U1") (pin "20") (pinfunction "SCK/CLK_20") (pintype "bidirectional"))
    )
    (net (code "108") (name "unconnected-(U1-SCS{slash}CMD-Pad19)") (class "Default")
      (node (ref "U1") (pin "19") (pinfunction "SCS/CMD_19") (pintype "bidirectional"))
    )
    (net (code "109") (name "unconnected-(U1-SDI{slash}SD1-Pad22)") (class "Default")
      (node (ref "U1") (pin "22") (pinfunction "SDI/SD1_22") (pintype "bidirectional"))
    )
    (net (code "110") (name "unconnected-(U1-SDO{slash}SD0-Pad21)") (class "Default")
      (node (ref "U1") (pin "21") (pinfunction "SDO/SD0_21") (pintype "bidirectional"))
    )
    (net (code "111") (name "unconnected-(U1-SHD{slash}SD2-Pad17)") (class "Default")
      (node (ref "U1") (pin "17") (pinfunction "SHD/SD2_17") (pintype "bidirectional"))
    )
    (net (code "112") (name "unconnected-(U1-SWP{slash}SD3-Pad18)") (class "Default")
      (node (ref "U1") (pin "18") (pinfunction "SWP/SD3_18") (pintype "bidirectional"))
    )
    (net (code "113") (name "unconnected-(U2-CTS-Pad18)") (class "Default")
      (node (ref "U2") (pin "18") (pinfunction "CTS_18") (pintype "input"))
    )
    (net (code "114") (name "unconnected-(U2-DCD-Pad24)") (class "Default")
      (node (ref "U2") (pin "24") (pinfunction "DCD_24") (pintype "bidirectional"))
    )
    (net (code "115") (name "unconnected-(U2-DSR-Pad22)") (class "Default")
      (node (ref "U2") (pin "22") (pinfunction "DSR_22") (pintype "bidirectional"))
    )
    (net (code "116") (name "unconnected-(U2-GPIO.0{slash}TXT-Pad14)") (class "Default")
      (node (ref "U2") (pin "14") (pinfunction "GPIO.0/TXT_14") (pintype "bidirectional"))
    )
    (net (code "117") (name "unconnected-(U2-GPIO.1{slash}RXT-Pad13)") (class "Default")
      (node (ref "U2") (pin "13") (pinfunction "GPIO.1/RXT_13") (pintype "bidirectional"))
    )
    (net (code "118") (name "unconnected-(U2-GPIO.2{slash}RS485-Pad12)") (class "Default")
      (node (ref "U2") (pin "12") (pinfunction "GPIO.2/RS485_12") (pintype "bidirectional"))
    )
    (net (code "119") (name "unconnected-(U2-GPIO.3{slash}WAKEUP-Pad11)") (class "Default")
      (node (ref "U2") (pin "11") (pinfunction "GPIO.3/WAKEUP_11") (pintype "bidirectional"))
    )
    (net (code "120") (name "unconnected-(U2-RI{slash}CLK-Pad1)") (class "Default")
      (node (ref "U2") (pin "1") (pinfunction "RI/CLK_1") (pintype "input"))
    )
    (net (code "121") (name "unconnected-(U2-SUSPEND-Pad17)") (class "Default")
      (node (ref "U2") (pin "17") (pinfunction "SUSPEND_17") (pintype "output"))
    )
    (net (code "122") (name "unconnected-(U2-VIO-Pad5)") (class "Default")
      (node (ref "U2") (pin "5") (pinfunction "VIO_5") (pintype "bidirectional"))
    )
    (net (code "123") (name "unconnected-(U2-~{RST}-Pad9)") (class "Default")
      (node (ref "U2") (pin "9") (pinfunction "~{RST}_9") (pintype "input"))
    )
    (net (code "124") (name "unconnected-(U2-~{SUSPEND}-Pad15)") (class "Default")
      (node (ref "U2") (pin "15") (pinfunction "~{SUSPEND}_15") (pintype "output"))
    )
  )
)
